# USB_Hub.net
KiCad netlist of a schematic drawn in Altium Designer
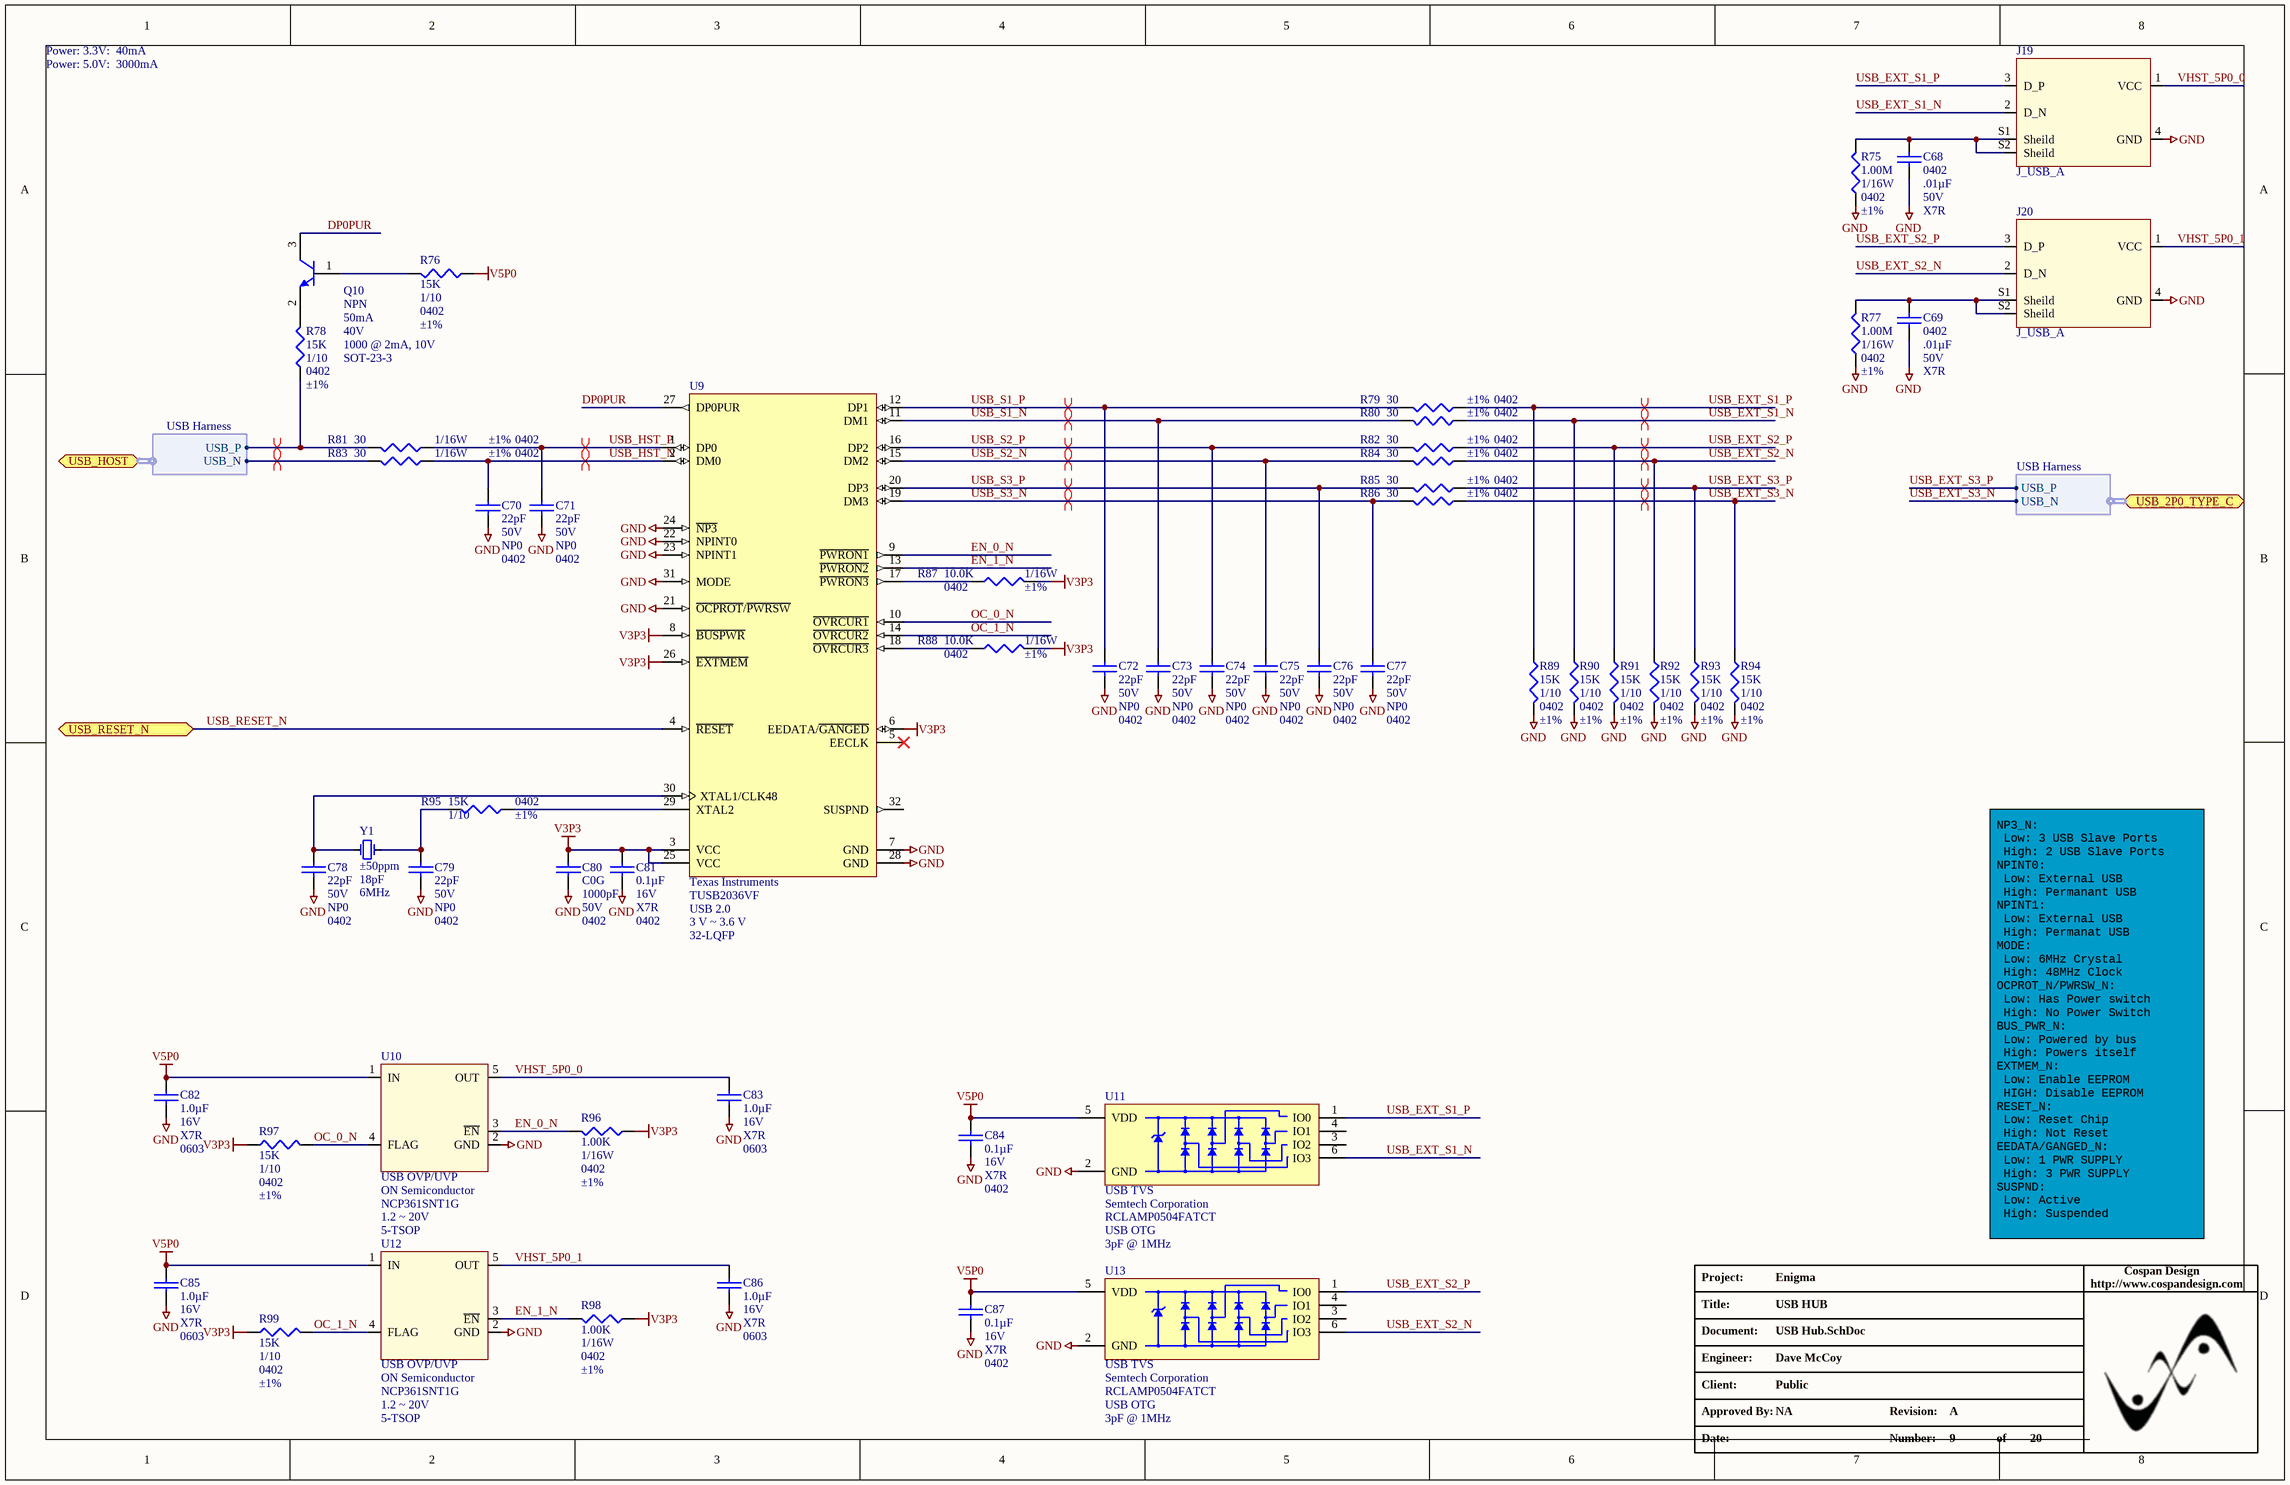
[diagram p0: USB Hub.SchDoc]

(export (version "E")
  (design (tool "Eeschema 10.0.6"))
  (components
    (comp (ref "C68")
      (value "10000pF")
      (footprint "C_0402")
      (description "CAP CERAMIC .01UF 50V X7R 0402")
      (fields
        (field (name "MANUFACTURER") "Murata Electronics North America")
        (field (name "MANUFACTURER PART NUMBER") "GRM155R71H103KA88D")
        (field (name "PACKAGE / CASE") "0402")
        (field (name "CAPACITANCE") ".01µF")
        (field (name "VOLTAGE - RATED") "50V")
        (field (name "TEMPERATURE COEFFICIENT") "X7R")
      )
      (libsource (lib "Main Library") (part "C_0402_10000PF_50V"))
    )
    (comp (ref "C69")
      (value "10000pF")
      (footprint "C_0402")
      (description "CAP CERAMIC .01UF 50V X7R 0402")
      (fields
        (field (name "MANUFACTURER") "Murata Electronics North America")
        (field (name "MANUFACTURER PART NUMBER") "GRM155R71H103KA88D")
        (field (name "PACKAGE / CASE") "0402")
        (field (name "CAPACITANCE") ".01µF")
        (field (name "VOLTAGE - RATED") "50V")
        (field (name "TEMPERATURE COEFFICIENT") "X7R")
      )
      (libsource (lib "Main Library") (part "C_0402_10000PF_50V"))
    )
    (comp (ref "C70")
      (value "22pF")
      (footprint "C_ERA-0402")
      (description "CAP CER 22PF 50V NP0 0402")
      (fields
        (field (name "MANUFACTURER") "Murata Electronics North America")
        (field (name "MANUFACTURER PART NUMBER") "GRM1555C1H220FA01D")
        (field (name "CAPACITANCE") "22pF")
        (field (name "VOLTAGE - RATED") "50V")
        (field (name "TEMPERATURE COEFFICIENT") "NP0")
        (field (name "PACKAGE / CASE") "0402")
      )
      (libsource (lib "Main LibraryX") (part "C_0402_22PF_50V"))
    )
    (comp (ref "C71")
      (value "22pF")
      (footprint "C_ERA-0402")
      (description "CAP CER 22PF 50V NP0 0402")
      (fields
        (field (name "MANUFACTURER") "Murata Electronics North America")
        (field (name "MANUFACTURER PART NUMBER") "GRM1555C1H220FA01D")
        (field (name "CAPACITANCE") "22pF")
        (field (name "VOLTAGE - RATED") "50V")
        (field (name "TEMPERATURE COEFFICIENT") "NP0")
        (field (name "PACKAGE / CASE") "0402")
      )
      (libsource (lib "Main LibraryX") (part "C_0402_22PF_50V"))
    )
    (comp (ref "C72")
      (value "22pF")
      (footprint "C_ERA-0402")
      (description "CAP CER 22PF 50V NP0 0402")
      (fields
        (field (name "MANUFACTURER") "Murata Electronics North America")
        (field (name "MANUFACTURER PART NUMBER") "GRM1555C1H220FA01D")
        (field (name "CAPACITANCE") "22pF")
        (field (name "VOLTAGE - RATED") "50V")
        (field (name "TEMPERATURE COEFFICIENT") "NP0")
        (field (name "PACKAGE / CASE") "0402")
      )
      (libsource (lib "Main LibraryX") (part "C_0402_22PF_50V"))
    )
    (comp (ref "C73")
      (value "22pF")
      (footprint "C_ERA-0402")
      (description "CAP CER 22PF 50V NP0 0402")
      (fields
        (field (name "MANUFACTURER") "Murata Electronics North America")
        (field (name "MANUFACTURER PART NUMBER") "GRM1555C1H220FA01D")
        (field (name "CAPACITANCE") "22pF")
        (field (name "VOLTAGE - RATED") "50V")
        (field (name "TEMPERATURE COEFFICIENT") "NP0")
        (field (name "PACKAGE / CASE") "0402")
      )
      (libsource (lib "Main LibraryX") (part "C_0402_22PF_50V"))
    )
    (comp (ref "C74")
      (value "22pF")
      (footprint "C_ERA-0402")
      (description "CAP CER 22PF 50V NP0 0402")
      (fields
        (field (name "MANUFACTURER") "Murata Electronics North America")
        (field (name "MANUFACTURER PART NUMBER") "GRM1555C1H220FA01D")
        (field (name "CAPACITANCE") "22pF")
        (field (name "VOLTAGE - RATED") "50V")
        (field (name "TEMPERATURE COEFFICIENT") "NP0")
        (field (name "PACKAGE / CASE") "0402")
      )
      (libsource (lib "Main LibraryX") (part "C_0402_22PF_50V"))
    )
    (comp (ref "C75")
      (value "22pF")
      (footprint "C_ERA-0402")
      (description "CAP CER 22PF 50V NP0 0402")
      (fields
        (field (name "MANUFACTURER") "Murata Electronics North America")
        (field (name "MANUFACTURER PART NUMBER") "GRM1555C1H220FA01D")
        (field (name "CAPACITANCE") "22pF")
        (field (name "VOLTAGE - RATED") "50V")
        (field (name "TEMPERATURE COEFFICIENT") "NP0")
        (field (name "PACKAGE / CASE") "0402")
      )
      (libsource (lib "Main LibraryX") (part "C_0402_22PF_50V"))
    )
    (comp (ref "C76")
      (value "22pF")
      (footprint "C_ERA-0402")
      (description "CAP CER 22PF 50V NP0 0402")
      (fields
        (field (name "MANUFACTURER") "Murata Electronics North America")
        (field (name "MANUFACTURER PART NUMBER") "GRM1555C1H220FA01D")
        (field (name "CAPACITANCE") "22pF")
        (field (name "VOLTAGE - RATED") "50V")
        (field (name "TEMPERATURE COEFFICIENT") "NP0")
        (field (name "PACKAGE / CASE") "0402")
      )
      (libsource (lib "Main LibraryX") (part "C_0402_22PF_50V"))
    )
    (comp (ref "C77")
      (value "22pF")
      (footprint "C_ERA-0402")
      (description "CAP CER 22PF 50V NP0 0402")
      (fields
        (field (name "MANUFACTURER") "Murata Electronics North America")
        (field (name "MANUFACTURER PART NUMBER") "GRM1555C1H220FA01D")
        (field (name "CAPACITANCE") "22pF")
        (field (name "VOLTAGE - RATED") "50V")
        (field (name "TEMPERATURE COEFFICIENT") "NP0")
        (field (name "PACKAGE / CASE") "0402")
      )
      (libsource (lib "Main LibraryX") (part "C_0402_22PF_50V"))
    )
    (comp (ref "C78")
      (value "22pF")
      (footprint "C_ERA-0402")
      (description "CAP CER 22PF 50V NP0 0402")
      (fields
        (field (name "MANUFACTURER") "Murata Electronics North America")
        (field (name "MANUFACTURER PART NUMBER") "GRM1555C1H220FA01D")
        (field (name "CAPACITANCE") "22pF")
        (field (name "VOLTAGE - RATED") "50V")
        (field (name "TEMPERATURE COEFFICIENT") "NP0")
        (field (name "PACKAGE / CASE") "0402")
      )
      (libsource (lib "Main LibraryX") (part "C_0402_22PF_50V"))
    )
    (comp (ref "C79")
      (value "22pF")
      (footprint "C_ERA-0402")
      (description "CAP CER 22PF 50V NP0 0402")
      (fields
        (field (name "MANUFACTURER") "Murata Electronics North America")
        (field (name "MANUFACTURER PART NUMBER") "GRM1555C1H220FA01D")
        (field (name "CAPACITANCE") "22pF")
        (field (name "VOLTAGE - RATED") "50V")
        (field (name "TEMPERATURE COEFFICIENT") "NP0")
        (field (name "PACKAGE / CASE") "0402")
      )
      (libsource (lib "Main LibraryX") (part "C_0402_22PF_50V"))
    )
    (comp (ref "C80")
      (value "1000pF")
      (footprint "C_0402")
      (description "CAP CER 1000PF 50V C0G 0402")
      (fields
        (field (name "MANUFACTURER") "Murata Electronics North America")
        (field (name "MANUFACTURER PART NUMBER") "GRM1555C1H102JA01D")
        (field (name "TEMPERATURE COEFFICIENT") "C0G")
        (field (name "CAPACITANCE") "1000pF")
        (field (name "VOLTAGE - RATED") "50V")
        (field (name "PACKAGE / CASE") "0402")
      )
      (libsource (lib "Main Library") (part "C_0402_1000PF_50V"))
    )
    (comp (ref "C81")
      (value "0.1uF")
      (footprint "C_0402")
      (description "CAP CER .10UF 16V X7R 0402")
      (fields
        (field (name "MANUFACTURER") "Murata Electronics North America")
        (field (name "MANUFACTURER PART NUMBER") "GRM155R71C104KA88J")
        (field (name "CAPACITANCE") "0.1µF")
        (field (name "VOLTAGE - RATED") "16V")
        (field (name "TEMPERATURE COEFFICIENT") "X7R")
        (field (name "PACKAGE / CASE") "0402")
      )
      (libsource (lib "Main LibraryX") (part "C_0402_0.1UF_16V"))
    )
    (comp (ref "C82")
      (value "1.0uF")
      (footprint "C_ERA-0603")
      (description "CAP CER 1UF 16V 10% X7R 0603")
      (fields
        (field (name "MANUFACTURER") "Yageo")
        (field (name "MANUFACTURER PART NUMBER") "CC0603KRX7R7BB105")
        (field (name "CAPACITANCE") "1.0µF")
        (field (name "VOLTAGE - RATED") "16V")
        (field (name "TEMPERATURE COEFFICIENT") "X7R")
        (field (name "PACKAGE / CASE") "0603")
      )
      (libsource (lib "Main LibraryX") (part "C_0603_1.0uF_16V"))
    )
    (comp (ref "C83")
      (value "1.0uF")
      (footprint "C_ERA-0603")
      (description "CAP CER 1UF 16V 10% X7R 0603")
      (fields
        (field (name "MANUFACTURER") "Yageo")
        (field (name "MANUFACTURER PART NUMBER") "CC0603KRX7R7BB105")
        (field (name "CAPACITANCE") "1.0µF")
        (field (name "VOLTAGE - RATED") "16V")
        (field (name "TEMPERATURE COEFFICIENT") "X7R")
        (field (name "PACKAGE / CASE") "0603")
      )
      (libsource (lib "Main LibraryX") (part "C_0603_1.0uF_16V"))
    )
    (comp (ref "C84")
      (value "0.1uF")
      (footprint "C_0402")
      (description "CAP CER .10UF 16V X7R 0402")
      (fields
        (field (name "MANUFACTURER") "Murata Electronics North America")
        (field (name "MANUFACTURER PART NUMBER") "GRM155R71C104KA88J")
        (field (name "CAPACITANCE") "0.1µF")
        (field (name "VOLTAGE - RATED") "16V")
        (field (name "TEMPERATURE COEFFICIENT") "X7R")
        (field (name "PACKAGE / CASE") "0402")
      )
      (libsource (lib "Main LibraryX") (part "C_0402_0.1UF_16V"))
    )
    (comp (ref "C85")
      (value "1.0uF")
      (footprint "C_ERA-0603")
      (description "CAP CER 1UF 16V 10% X7R 0603")
      (fields
        (field (name "MANUFACTURER") "Yageo")
        (field (name "MANUFACTURER PART NUMBER") "CC0603KRX7R7BB105")
        (field (name "CAPACITANCE") "1.0µF")
        (field (name "VOLTAGE - RATED") "16V")
        (field (name "TEMPERATURE COEFFICIENT") "X7R")
        (field (name "PACKAGE / CASE") "0603")
      )
      (libsource (lib "Main LibraryX") (part "C_0603_1.0uF_16V"))
    )
    (comp (ref "C86")
      (value "1.0uF")
      (footprint "C_ERA-0603")
      (description "CAP CER 1UF 16V 10% X7R 0603")
      (fields
        (field (name "MANUFACTURER") "Yageo")
        (field (name "MANUFACTURER PART NUMBER") "CC0603KRX7R7BB105")
        (field (name "CAPACITANCE") "1.0µF")
        (field (name "VOLTAGE - RATED") "16V")
        (field (name "TEMPERATURE COEFFICIENT") "X7R")
        (field (name "PACKAGE / CASE") "0603")
      )
      (libsource (lib "Main LibraryX") (part "C_0603_1.0uF_16V"))
    )
    (comp (ref "C87")
      (value "0.1uF")
      (footprint "C_0402")
      (description "CAP CER .10UF 16V X7R 0402")
      (fields
        (field (name "MANUFACTURER") "Murata Electronics North America")
        (field (name "MANUFACTURER PART NUMBER") "GRM155R71C104KA88J")
        (field (name "CAPACITANCE") "0.1µF")
        (field (name "VOLTAGE - RATED") "16V")
        (field (name "TEMPERATURE COEFFICIENT") "X7R")
        (field (name "PACKAGE / CASE") "0402")
      )
      (libsource (lib "Main LibraryX") (part "C_0402_0.1UF_16V"))
    )
    (comp (ref "J19")
      (value "J_USB_A")
      (footprint "USB_A")
      (description "CONN PLUG USB A 4POS SMD R/A")
      (fields
        (field (name "MANUFACTURER") "Molex Inc")
        (field (name "MANUFACTURER PART NUMBER") "0480372200")
      )
      (libsource (lib "Main Library") (part "J_USB_A"))
    )
    (comp (ref "J20")
      (value "J_USB_A")
      (footprint "USB_A")
      (description "CONN PLUG USB A 4POS SMD R/A")
      (fields
        (field (name "MANUFACTURER") "Molex Inc")
        (field (name "MANUFACTURER PART NUMBER") "0480372200")
      )
      (libsource (lib "Main Library") (part "J_USB_A"))
    )
    (comp (ref "Q10")
      (value "NPN")
      (footprint "SOT-23A")
      (description "TRANS NPN 40V 50MA MINI3")
      (fields
        (field (name "MANUFACTURER") "Panasonic Electronic Components - Semiconductor Products")
        (field (name "MANUFACTURER PART NUMBER") "DSC2A01T0L")
        (field (name "TRANSISTOR TYPE") "NPN")
        (field (name "CURRENT - COLLECTOR (IC) (MAX)") "50mA")
        (field (name "VOLTAGE - COLLECTOR EMITTER BREAKDOWN (MAX)") "40V")
        (field (name "DC CURRENT GAIN (HFE) (MIN) @ IC, VCE") "1000 @ 2mA, 10V")
        (field (name "PACKAGE / CASE") "SOT-23-3")
      )
      (libsource (lib "Main Library") (part "Q_NPN_40MA_HFE_1000"))
    )
    (comp (ref "R75")
      (value "1.0M Ohms")
      (footprint "R_0402")
      (description "RES 1.00M OHM 1/16W 1% 0402 SMD")
      (fields
        (field (name "MANUFACTURER") "Yageo")
        (field (name "MANUFACTURER PART NUMBER") "RC0402FR-071ML")
        (field (name "RESISTANCE IN OHMS") "1.00M")
        (field (name "POWER (WATTS)") "1/16W")
        (field (name "CASE") "0402")
        (field (name "TOLERANCE") "±1%")
      )
      (libsource (lib "Main LibraryX") (part "R_0402_1.0M"))
    )
    (comp (ref "R76")
      (value "R_0402_15.0K")
      (footprint "R_0402")
      (description "RES 15.0K OHM 1/10W 1% 0402 SMD")
      (fields
        (field (name "MANUFACTURER") "Panasonic - ECG")
        (field (name "MANUFACTURER PART NUMBER") "ERJ-2RKF1502X")
        (field (name "RESISTANCE IN OHMS") "15K")
        (field (name "POWER (WATTS)") "1/10")
        (field (name "CASE") "0402")
        (field (name "TOLERANCE") "±1%")
      )
      (libsource (lib "Main Library") (part "R_0402_15.0K"))
    )
    (comp (ref "R77")
      (value "1.0M Ohms")
      (footprint "R_0402")
      (description "RES 1.00M OHM 1/16W 1% 0402 SMD")
      (fields
        (field (name "MANUFACTURER") "Yageo")
        (field (name "MANUFACTURER PART NUMBER") "RC0402FR-071ML")
        (field (name "RESISTANCE IN OHMS") "1.00M")
        (field (name "POWER (WATTS)") "1/16W")
        (field (name "CASE") "0402")
        (field (name "TOLERANCE") "±1%")
      )
      (libsource (lib "Main LibraryX") (part "R_0402_1.0M"))
    )
    (comp (ref "R78")
      (value "R_0402_15.0K")
      (footprint "R_0402")
      (description "RES 15.0K OHM 1/10W 1% 0402 SMD")
      (fields
        (field (name "MANUFACTURER") "Panasonic - ECG")
        (field (name "MANUFACTURER PART NUMBER") "ERJ-2RKF1502X")
        (field (name "RESISTANCE IN OHMS") "15K")
        (field (name "POWER (WATTS)") "1/10")
        (field (name "CASE") "0402")
        (field (name "TOLERANCE") "±1%")
      )
      (libsource (lib "Main Library") (part "R_0402_15.0K"))
    )
    (comp (ref "R79")
      (value "R_0402_30")
      (footprint "R_0402")
      (description "RES SMD 30 OHM 1% 1/10W 0402")
      (fields
        (field (name "MANUFACTURER") "Panasonic Electronic Components")
        (field (name "MANUFACTURER PART NUMBER") "ERJ-2RKF30R0X")
        (field (name "RESISTANCE IN OHMS") "30")
        (field (name "CASE") "0402")
        (field (name "TOLERANCE") "±1%")
      )
      (libsource (lib "Cospan Design") (part "R_0402_30"))
    )
    (comp (ref "R80")
      (value "R_0402_30")
      (footprint "R_0402")
      (description "RES SMD 30 OHM 1% 1/10W 0402")
      (fields
        (field (name "MANUFACTURER") "Panasonic Electronic Components")
        (field (name "MANUFACTURER PART NUMBER") "ERJ-2RKF30R0X")
        (field (name "RESISTANCE IN OHMS") "30")
        (field (name "CASE") "0402")
        (field (name "TOLERANCE") "±1%")
      )
      (libsource (lib "Cospan Design") (part "R_0402_30"))
    )
    (comp (ref "R81")
      (value "R_0402_30")
      (footprint "R_0402")
      (description "RES SMD 30 OHM 1% 1/10W 0402")
      (fields
        (field (name "MANUFACTURER") "Panasonic Electronic Components")
        (field (name "MANUFACTURER PART NUMBER") "ERJ-2RKF30R0X")
        (field (name "RESISTANCE IN OHMS") "30")
        (field (name "POWER (WATTS)") "1/16W")
        (field (name "CASE") "0402")
        (field (name "TOLERANCE") "±1%")
      )
      (libsource (lib "Cospan Design") (part "R_0402_30"))
    )
    (comp (ref "R82")
      (value "R_0402_30")
      (footprint "R_0402")
      (description "RES SMD 30 OHM 1% 1/10W 0402")
      (fields
        (field (name "MANUFACTURER") "Panasonic Electronic Components")
        (field (name "MANUFACTURER PART NUMBER") "ERJ-2RKF30R0X")
        (field (name "RESISTANCE IN OHMS") "30")
        (field (name "CASE") "0402")
        (field (name "TOLERANCE") "±1%")
      )
      (libsource (lib "Cospan Design") (part "R_0402_30"))
    )
    (comp (ref "R83")
      (value "R_0402_30")
      (footprint "R_0402")
      (description "RES SMD 30 OHM 1% 1/10W 0402")
      (fields
        (field (name "MANUFACTURER") "Panasonic Electronic Components")
        (field (name "MANUFACTURER PART NUMBER") "ERJ-2RKF30R0X")
        (field (name "RESISTANCE IN OHMS") "30")
        (field (name "POWER (WATTS)") "1/16W")
        (field (name "CASE") "0402")
        (field (name "TOLERANCE") "±1%")
      )
      (libsource (lib "Cospan Design") (part "R_0402_30"))
    )
    (comp (ref "R84")
      (value "R_0402_30")
      (footprint "R_0402")
      (description "RES SMD 30 OHM 1% 1/10W 0402")
      (fields
        (field (name "MANUFACTURER") "Panasonic Electronic Components")
        (field (name "MANUFACTURER PART NUMBER") "ERJ-2RKF30R0X")
        (field (name "RESISTANCE IN OHMS") "30")
        (field (name "CASE") "0402")
        (field (name "TOLERANCE") "±1%")
      )
      (libsource (lib "Cospan Design") (part "R_0402_30"))
    )
    (comp (ref "R85")
      (value "R_0402_30")
      (footprint "R_0402")
      (description "RES SMD 30 OHM 1% 1/10W 0402")
      (fields
        (field (name "MANUFACTURER") "Panasonic Electronic Components")
        (field (name "MANUFACTURER PART NUMBER") "ERJ-2RKF30R0X")
        (field (name "RESISTANCE IN OHMS") "30")
        (field (name "CASE") "0402")
        (field (name "TOLERANCE") "±1%")
      )
      (libsource (lib "Cospan Design") (part "R_0402_30"))
    )
    (comp (ref "R86")
      (value "R_0402_30")
      (footprint "R_0402")
      (description "RES SMD 30 OHM 1% 1/10W 0402")
      (fields
        (field (name "MANUFACTURER") "Panasonic Electronic Components")
        (field (name "MANUFACTURER PART NUMBER") "ERJ-2RKF30R0X")
        (field (name "RESISTANCE IN OHMS") "30")
        (field (name "CASE") "0402")
        (field (name "TOLERANCE") "±1%")
      )
      (libsource (lib "Cospan Design") (part "R_0402_30"))
    )
    (comp (ref "R87")
      (value "R_0402_10.0K")
      (footprint "R_0402")
      (description "RES 10.0K OHM 1/16W 1% 0402 SMD")
      (fields
        (field (name "MANUFACTURER") "Stackpole Electronics Inc")
        (field (name "MANUFACTURER PART NUMBER") "RMCF0402FT10K0")
        (field (name "RESISTANCE IN OHMS") "10.0K")
        (field (name "POWER (WATTS)") "1/16W")
        (field (name "CASE") "0402")
        (field (name "TOLERANCE") "±1%")
      )
      (libsource (lib "Cospan Design") (part "R_0402_10.0K"))
    )
    (comp (ref "R88")
      (value "R_0402_10.0K")
      (footprint "R_0402")
      (description "RES 10.0K OHM 1/16W 1% 0402 SMD")
      (fields
        (field (name "MANUFACTURER") "Stackpole Electronics Inc")
        (field (name "MANUFACTURER PART NUMBER") "RMCF0402FT10K0")
        (field (name "RESISTANCE IN OHMS") "10.0K")
        (field (name "POWER (WATTS)") "1/16W")
        (field (name "CASE") "0402")
        (field (name "TOLERANCE") "±1%")
      )
      (libsource (lib "Cospan Design") (part "R_0402_10.0K"))
    )
    (comp (ref "R89")
      (value "R_0402_15.0K")
      (footprint "R_0402")
      (description "RES 15.0K OHM 1/10W 1% 0402 SMD")
      (fields
        (field (name "MANUFACTURER") "Panasonic - ECG")
        (field (name "MANUFACTURER PART NUMBER") "ERJ-2RKF1502X")
        (field (name "RESISTANCE IN OHMS") "15K")
        (field (name "POWER (WATTS)") "1/10")
        (field (name "CASE") "0402")
        (field (name "TOLERANCE") "±1%")
      )
      (libsource (lib "Main Library") (part "R_0402_15.0K"))
    )
    (comp (ref "R90")
      (value "R_0402_15.0K")
      (footprint "R_0402")
      (description "RES 15.0K OHM 1/10W 1% 0402 SMD")
      (fields
        (field (name "MANUFACTURER") "Panasonic - ECG")
        (field (name "MANUFACTURER PART NUMBER") "ERJ-2RKF1502X")
        (field (name "RESISTANCE IN OHMS") "15K")
        (field (name "POWER (WATTS)") "1/10")
        (field (name "CASE") "0402")
        (field (name "TOLERANCE") "±1%")
      )
      (libsource (lib "Main Library") (part "R_0402_15.0K"))
    )
    (comp (ref "R91")
      (value "R_0402_15.0K")
      (footprint "R_0402")
      (description "RES 15.0K OHM 1/10W 1% 0402 SMD")
      (fields
        (field (name "MANUFACTURER") "Panasonic - ECG")
        (field (name "MANUFACTURER PART NUMBER") "ERJ-2RKF1502X")
        (field (name "RESISTANCE IN OHMS") "15K")
        (field (name "POWER (WATTS)") "1/10")
        (field (name "CASE") "0402")
        (field (name "TOLERANCE") "±1%")
      )
      (libsource (lib "Main Library") (part "R_0402_15.0K"))
    )
    (comp (ref "R92")
      (value "R_0402_15.0K")
      (footprint "R_0402")
      (description "RES 15.0K OHM 1/10W 1% 0402 SMD")
      (fields
        (field (name "MANUFACTURER") "Panasonic - ECG")
        (field (name "MANUFACTURER PART NUMBER") "ERJ-2RKF1502X")
        (field (name "RESISTANCE IN OHMS") "15K")
        (field (name "POWER (WATTS)") "1/10")
        (field (name "CASE") "0402")
        (field (name "TOLERANCE") "±1%")
      )
      (libsource (lib "Main Library") (part "R_0402_15.0K"))
    )
    (comp (ref "R93")
      (value "R_0402_15.0K")
      (footprint "R_0402")
      (description "RES 15.0K OHM 1/10W 1% 0402 SMD")
      (fields
        (field (name "MANUFACTURER") "Panasonic - ECG")
        (field (name "MANUFACTURER PART NUMBER") "ERJ-2RKF1502X")
        (field (name "RESISTANCE IN OHMS") "15K")
        (field (name "POWER (WATTS)") "1/10")
        (field (name "CASE") "0402")
        (field (name "TOLERANCE") "±1%")
      )
      (libsource (lib "Main Library") (part "R_0402_15.0K"))
    )
    (comp (ref "R94")
      (value "R_0402_15.0K")
      (footprint "R_0402")
      (description "RES 15.0K OHM 1/10W 1% 0402 SMD")
      (fields
        (field (name "MANUFACTURER") "Panasonic - ECG")
        (field (name "MANUFACTURER PART NUMBER") "ERJ-2RKF1502X")
        (field (name "RESISTANCE IN OHMS") "15K")
        (field (name "POWER (WATTS)") "1/10")
        (field (name "CASE") "0402")
        (field (name "TOLERANCE") "±1%")
      )
      (libsource (lib "Main Library") (part "R_0402_15.0K"))
    )
    (comp (ref "R95")
      (value "R_0402_15.0K")
      (footprint "R_0402")
      (description "RES 15.0K OHM 1/10W 1% 0402 SMD")
      (fields
        (field (name "MANUFACTURER") "Panasonic - ECG")
        (field (name "MANUFACTURER PART NUMBER") "ERJ-2RKF1502X")
        (field (name "RESISTANCE IN OHMS") "15K")
        (field (name "POWER (WATTS)") "1/10")
        (field (name "CASE") "0402")
        (field (name "TOLERANCE") "±1%")
      )
      (libsource (lib "Main Library") (part "R_0402_15.0K"))
    )
    (comp (ref "R96")
      (value "1.0k Ohms")
      (footprint "R_0402")
      (description "RES 1.00K OHM 1/16W 1% 0402 SMD")
      (fields
        (field (name "MANUFACTURER") "Yageo")
        (field (name "MANUFACTURER PART NUMBER") "RC0402FR-071KL")
        (field (name "RESISTANCE IN OHMS") "1.00K")
        (field (name "POWER (WATTS)") "1/16W")
        (field (name "CASE") "0402")
        (field (name "TOLERANCE") "±1%")
      )
      (libsource (lib "Main Library") (part "R_0402_1.0K"))
    )
    (comp (ref "R97")
      (value "R_0402_15.0K")
      (footprint "R_0402")
      (description "RES 15.0K OHM 1/10W 1% 0402 SMD")
      (fields
        (field (name "MANUFACTURER") "Panasonic - ECG")
        (field (name "MANUFACTURER PART NUMBER") "ERJ-2RKF1502X")
        (field (name "RESISTANCE IN OHMS") "15K")
        (field (name "POWER (WATTS)") "1/10")
        (field (name "CASE") "0402")
        (field (name "TOLERANCE") "±1%")
      )
      (libsource (lib "Main Library") (part "R_0402_15.0K"))
    )
    (comp (ref "R98")
      (value "1.0k Ohms")
      (footprint "R_0402")
      (description "RES 1.00K OHM 1/16W 1% 0402 SMD")
      (fields
        (field (name "MANUFACTURER") "Yageo")
        (field (name "MANUFACTURER PART NUMBER") "RC0402FR-071KL")
        (field (name "RESISTANCE IN OHMS") "1.00K")
        (field (name "POWER (WATTS)") "1/16W")
        (field (name "CASE") "0402")
        (field (name "TOLERANCE") "±1%")
      )
      (libsource (lib "Main Library") (part "R_0402_1.0K"))
    )
    (comp (ref "R99")
      (value "R_0402_15.0K")
      (footprint "R_0402")
      (description "RES 15.0K OHM 1/10W 1% 0402 SMD")
      (fields
        (field (name "MANUFACTURER") "Panasonic - ECG")
        (field (name "MANUFACTURER PART NUMBER") "ERJ-2RKF1502X")
        (field (name "RESISTANCE IN OHMS") "15K")
        (field (name "POWER (WATTS)") "1/10")
        (field (name "CASE") "0402")
        (field (name "TOLERANCE") "±1%")
      )
      (libsource (lib "Main Library") (part "R_0402_15.0K"))
    )
    (comp (ref "U9")
      (value "U_TI-TUSB2036-LQFP_VF-32")
      (footprint "VF32_L")
      (description "IC HUB CONTROLLER USB 2.0 32LQFP")
      (fields
        (field (name "MANUFACTURER") "Texas Instruments")
        (field (name "MANUFACTURER PART NUMBER") "TUSB2036VF")
        (field (name "STANDARDS") "USB 2.0")
        (field (name "VOLTAGE - SUPPLY") "3 V ~ 3.6 V")
        (field (name "PACKAGE / CASE") "32-LQFP")
      )
      (libsource (lib "Cospan Design") (part "U_TI-TUSB2036-LQFP_VF-32"))
    )
    (comp (ref "U10")
      (value "USB OVP/UVP")
      (footprint "SOT95P280X90-5N")
      (description "IC USB POS OVP/OCP 5TSOP")
      (fields
        (field (name "MANUFACTURER") "ON Semiconductor")
        (field (name "MANUFACTURER PART NUMBER") "NCP361SNT1G")
        (field (name "VOLTAGE - WORKING") "1.2 ~ 20V")
        (field (name "SUPPLIER DEVICE PACKAGE") "5-TSOP")
      )
      (libsource (lib "Main Library") (part "U_NCP361SNT1G"))
    )
    (comp (ref "U11")
      (value "USB TVS")
      (footprint "SC70-LT6_N")
      (description "TVS DIODE 5VWM 25VC SC70-6")
      (fields
        (field (name "MANUFACTURER") "Semtech Corporation")
        (field (name "MANUFACTURER PART NUMBER") "RCLAMP0504FATCT")
        (field (name "APPLICATIONS") "USB OTG")
        (field (name "CAPACITANCE @ FREQUENCY") "3pF @ 1MHz")
      )
      (libsource (lib "Main Library") (part "U_USB_TVS_SCV70"))
    )
    (comp (ref "U12")
      (value "USB OVP/UVP")
      (footprint "SOT95P280X90-5N")
      (description "IC USB POS OVP/OCP 5TSOP")
      (fields
        (field (name "MANUFACTURER") "ON Semiconductor")
        (field (name "MANUFACTURER PART NUMBER") "NCP361SNT1G")
        (field (name "VOLTAGE - WORKING") "1.2 ~ 20V")
        (field (name "SUPPLIER DEVICE PACKAGE") "5-TSOP")
      )
      (libsource (lib "Main Library") (part "U_NCP361SNT1G"))
    )
    (comp (ref "U13")
      (value "USB TVS")
      (footprint "SC70-LT6_N")
      (description "TVS DIODE 5VWM 25VC SC70-6")
      (fields
        (field (name "MANUFACTURER") "Semtech Corporation")
        (field (name "MANUFACTURER PART NUMBER") "RCLAMP0504FATCT")
        (field (name "APPLICATIONS") "USB OTG")
        (field (name "CAPACITANCE @ FREQUENCY") "3pF @ 1MHz")
      )
      (libsource (lib "Main Library") (part "U_USB_TVS_SCV70"))
    )
    (comp (ref "Y1")
      (value "6.00MHz Crystal")
      (footprint "HC49")
      (description "CRYSTAL 6.0000MHZ 18PF SMD")
      (fields
        (field (name "MANUFACTURER") "Abracon LLC")
        (field (name "MANUFACTURER PART NUMBER") "ABLS-6.000MHZ-D-T")
        (field (name "FREQUENCY STABILITY") "±50ppm")
        (field (name "LOAD CAPACITANCE") "18pF")
        (field (name "FREQUENCY") "6MHz")
      )
      (libsource (lib "Main Library") (part "Y_SMD_6.00MHZ_18PF"))
    )
  )
  (nets
    (net (code "3") (name "/DP0PUR") (class "Default")
      (node (ref "Q10") (pin "3") (pinfunction "C_3") (pintype "passive"))
      (node (ref "U9") (pin "27") (pinfunction "DP0PUR_27") (pintype "output"))
    )
    (net (code "4") (name "/EN_0_N") (class "Default")
      (node (ref "R96") (pin "1") (pinfunction "1_1") (pintype "passive"))
      (node (ref "U10") (pin "3") (pinfunction "~{EN}_3") (pintype "passive"))
      (node (ref "U9") (pin "9") (pinfunction "~{PWRON1}_9") (pintype "output"))
    )
    (net (code "5") (name "/EN_1_N") (class "Default")
      (node (ref "R98") (pin "1") (pinfunction "1_1") (pintype "passive"))
      (node (ref "U12") (pin "3") (pinfunction "~{EN}_3") (pintype "passive"))
      (node (ref "U9") (pin "13") (pinfunction "~{PWRON2}_13") (pintype "output"))
    )
    (net (code "6") (name "/OC_0_N") (class "Default")
      (node (ref "R97") (pin "1") (pinfunction "1_1") (pintype "passive"))
      (node (ref "U10") (pin "4") (pinfunction "FLAG_4") (pintype "passive"))
      (node (ref "U9") (pin "10") (pinfunction "~{OVRCUR1}_10") (pintype "input"))
    )
    (net (code "7") (name "/OC_1_N") (class "Default")
      (node (ref "R99") (pin "1") (pinfunction "1_1") (pintype "passive"))
      (node (ref "U12") (pin "4") (pinfunction "FLAG_4") (pintype "passive"))
      (node (ref "U9") (pin "14") (pinfunction "~{OVRCUR2}_14") (pintype "input"))
    )
    (net (code "8") (name "/USB_EXT_S1_N") (class "Default")
      (node (ref "J19") (pin "2") (pinfunction "D_N_2") (pintype "passive"))
      (node (ref "R80") (pin "2") (pinfunction "2_2") (pintype "passive"))
      (node (ref "R90") (pin "2") (pinfunction "2_2") (pintype "passive"))
      (node (ref "U11") (pin "6") (pinfunction "IO3_6") (pintype "passive"))
    )
    (net (code "9") (name "/USB_EXT_S1_P") (class "Default")
      (node (ref "J19") (pin "3") (pinfunction "D_P_3") (pintype "passive"))
      (node (ref "R79") (pin "2") (pinfunction "2_2") (pintype "passive"))
      (node (ref "R89") (pin "2") (pinfunction "2_2") (pintype "passive"))
      (node (ref "U11") (pin "1") (pinfunction "IO0_1") (pintype "passive"))
    )
    (net (code "10") (name "/USB_EXT_S2_N") (class "Default")
      (node (ref "J20") (pin "2") (pinfunction "D_N_2") (pintype "passive"))
      (node (ref "R84") (pin "2") (pinfunction "2_2") (pintype "passive"))
      (node (ref "R92") (pin "2") (pinfunction "2_2") (pintype "passive"))
      (node (ref "U13") (pin "6") (pinfunction "IO3_6") (pintype "passive"))
    )
    (net (code "11") (name "/USB_EXT_S2_P") (class "Default")
      (node (ref "J20") (pin "3") (pinfunction "D_P_3") (pintype "passive"))
      (node (ref "R82") (pin "2") (pinfunction "2_2") (pintype "passive"))
      (node (ref "R91") (pin "2") (pinfunction "2_2") (pintype "passive"))
      (node (ref "U13") (pin "1") (pinfunction "IO0_1") (pintype "passive"))
    )
    (net (code "12") (name "/USB_EXT_S3_N") (class "Default")
      (node (ref "R86") (pin "2") (pinfunction "2_2") (pintype "passive"))
      (node (ref "R94") (pin "2") (pinfunction "2_2") (pintype "passive"))
    )
    (net (code "13") (name "/USB_EXT_S3_P") (class "Default")
      (node (ref "R85") (pin "2") (pinfunction "2_2") (pintype "passive"))
      (node (ref "R93") (pin "2") (pinfunction "2_2") (pintype "passive"))
    )
    (net (code "14") (name "/USB_HST_N") (class "Default")
      (node (ref "C70") (pin "2") (pinfunction "2_2") (pintype "passive"))
      (node (ref "R83") (pin "2") (pinfunction "2_2") (pintype "passive"))
      (node (ref "U9") (pin "2") (pinfunction "DM0_2") (pintype "bidirectional"))
    )
    (net (code "15") (name "/USB_HST_P") (class "Default")
      (node (ref "C71") (pin "2") (pinfunction "2_2") (pintype "passive"))
      (node (ref "R81") (pin "2") (pinfunction "2_2") (pintype "passive"))
      (node (ref "U9") (pin "1") (pinfunction "DP0_1") (pintype "bidirectional"))
    )
    (net (code "16") (name "/USB_RESET_N") (class "Default")
      (node (ref "U9") (pin "4") (pinfunction "~{RESET}_4") (pintype "input"))
    )
    (net (code "17") (name "/USB_S1_N") (class "Default")
      (node (ref "C73") (pin "2") (pinfunction "2_2") (pintype "passive"))
      (node (ref "R80") (pin "1") (pinfunction "1_1") (pintype "passive"))
      (node (ref "U9") (pin "11") (pinfunction "DM1_11") (pintype "bidirectional"))
    )
    (net (code "18") (name "/USB_S1_P") (class "Default")
      (node (ref "C72") (pin "2") (pinfunction "2_2") (pintype "passive"))
      (node (ref "R79") (pin "1") (pinfunction "1_1") (pintype "passive"))
      (node (ref "U9") (pin "12") (pinfunction "DP1_12") (pintype "bidirectional"))
    )
    (net (code "19") (name "/USB_S2_N") (class "Default")
      (node (ref "C75") (pin "2") (pinfunction "2_2") (pintype "passive"))
      (node (ref "R84") (pin "1") (pinfunction "1_1") (pintype "passive"))
      (node (ref "U9") (pin "15") (pinfunction "DM2_15") (pintype "bidirectional"))
    )
    (net (code "20") (name "/USB_S2_P") (class "Default")
      (node (ref "C74") (pin "2") (pinfunction "2_2") (pintype "passive"))
      (node (ref "R82") (pin "1") (pinfunction "1_1") (pintype "passive"))
      (node (ref "U9") (pin "16") (pinfunction "DP2_16") (pintype "bidirectional"))
    )
    (net (code "21") (name "/USB_S3_N") (class "Default")
      (node (ref "C77") (pin "2") (pinfunction "2_2") (pintype "passive"))
      (node (ref "R86") (pin "1") (pinfunction "1_1") (pintype "passive"))
      (node (ref "U9") (pin "19") (pinfunction "DM3_19") (pintype "bidirectional"))
    )
    (net (code "22") (name "/USB_S3_P") (class "Default")
      (node (ref "C76") (pin "2") (pinfunction "2_2") (pintype "passive"))
      (node (ref "R85") (pin "1") (pinfunction "1_1") (pintype "passive"))
      (node (ref "U9") (pin "20") (pinfunction "DP3_20") (pintype "bidirectional"))
    )
    (net (code "23") (name "/VHST_5P0_0") (class "Default")
      (node (ref "C83") (pin "2") (pinfunction "2_2") (pintype "passive"))
      (node (ref "J19") (pin "1") (pinfunction "VCC_1") (pintype "passive"))
      (node (ref "U10") (pin "5") (pinfunction "OUT_5") (pintype "passive"))
    )
    (net (code "24") (name "/VHST_5P0_1") (class "Default")
      (node (ref "C86") (pin "2") (pinfunction "2_2") (pintype "passive"))
      (node (ref "J20") (pin "1") (pinfunction "VCC_1") (pintype "passive"))
      (node (ref "U12") (pin "5") (pinfunction "OUT_5") (pintype "passive"))
    )
    (net (code "26") (name "GND") (class "Default")
      (node (ref "C68") (pin "1") (pinfunction "1_1") (pintype "passive"))
      (node (ref "C69") (pin "1") (pinfunction "1_1") (pintype "passive"))
      (node (ref "C70") (pin "1") (pinfunction "1_1") (pintype "passive"))
      (node (ref "C71") (pin "1") (pinfunction "1_1") (pintype "passive"))
      (node (ref "C72") (pin "1") (pinfunction "1_1") (pintype "passive"))
      (node (ref "C73") (pin "1") (pinfunction "1_1") (pintype "passive"))
      (node (ref "C74") (pin "1") (pinfunction "1_1") (pintype "passive"))
      (node (ref "C75") (pin "1") (pinfunction "1_1") (pintype "passive"))
      (node (ref "C76") (pin "1") (pinfunction "1_1") (pintype "passive"))
      (node (ref "C77") (pin "1") (pinfunction "1_1") (pintype "passive"))
      (node (ref "C78") (pin "1") (pinfunction "1_1") (pintype "passive"))
      (node (ref "C79") (pin "1") (pinfunction "1_1") (pintype "passive"))
      (node (ref "C80") (pin "1") (pinfunction "1_1") (pintype "passive"))
      (node (ref "C81") (pin "1") (pinfunction "1_1") (pintype "passive"))
      (node (ref "C82") (pin "1") (pinfunction "1_1") (pintype "passive"))
      (node (ref "C83") (pin "1") (pinfunction "1_1") (pintype "passive"))
      (node (ref "C84") (pin "1") (pinfunction "1_1") (pintype "passive"))
      (node (ref "C85") (pin "1") (pinfunction "1_1") (pintype "passive"))
      (node (ref "C86") (pin "1") (pinfunction "1_1") (pintype "passive"))
      (node (ref "C87") (pin "1") (pinfunction "1_1") (pintype "passive"))
      (node (ref "J19") (pin "4") (pinfunction "GND_4") (pintype "passive"))
      (node (ref "J20") (pin "4") (pinfunction "GND_4") (pintype "passive"))
      (node (ref "R75") (pin "2") (pinfunction "2_2") (pintype "passive"))
      (node (ref "R77") (pin "2") (pinfunction "2_2") (pintype "passive"))
      (node (ref "R89") (pin "1") (pinfunction "1_1") (pintype "passive"))
      (node (ref "R90") (pin "1") (pinfunction "1_1") (pintype "passive"))
      (node (ref "R91") (pin "1") (pinfunction "1_1") (pintype "passive"))
      (node (ref "R92") (pin "1") (pinfunction "1_1") (pintype "passive"))
      (node (ref "R93") (pin "1") (pinfunction "1_1") (pintype "passive"))
      (node (ref "R94") (pin "1") (pinfunction "1_1") (pintype "passive"))
      (node (ref "U10") (pin "2") (pinfunction "GND_2") (pintype "passive"))
      (node (ref "U11") (pin "2") (pinfunction "GND_2") (pintype "passive"))
      (node (ref "U12") (pin "2") (pinfunction "GND_2") (pintype "passive"))
      (node (ref "U13") (pin "2") (pinfunction "GND_2") (pintype "passive"))
      (node (ref "U9") (pin "21") (pinfunction "~{OCPROT}/~{PWRSW}_21") (pintype "input"))
      (node (ref "U9") (pin "22") (pinfunction "NPINT0_22") (pintype "input"))
      (node (ref "U9") (pin "23") (pinfunction "NPINT1_23") (pintype "input"))
      (node (ref "U9") (pin "24") (pinfunction "~{NP3}_24") (pintype "input"))
      (node (ref "U9") (pin "28") (pinfunction "GND_28") (pintype "power_in"))
      (node (ref "U9") (pin "31") (pinfunction "MODE_31") (pintype "input"))
      (node (ref "U9") (pin "7") (pinfunction "GND_7") (pintype "power_in"))
    )
    (net (code "27") (name "Net-(C68-Pad2)") (class "Default")
      (node (ref "C68") (pin "2") (pinfunction "2_2") (pintype "passive"))
      (node (ref "J19") (pin "S1") (pinfunction "Sheild_S1") (pintype "passive"))
      (node (ref "J19") (pin "S2") (pinfunction "Sheild_S2") (pintype "passive"))
      (node (ref "R75") (pin "1") (pinfunction "1_1") (pintype "passive"))
    )
    (net (code "28") (name "Net-(C69-Pad2)") (class "Default")
      (node (ref "C69") (pin "2") (pinfunction "2_2") (pintype "passive"))
      (node (ref "J20") (pin "S1") (pinfunction "Sheild_S1") (pintype "passive"))
      (node (ref "J20") (pin "S2") (pinfunction "Sheild_S2") (pintype "passive"))
      (node (ref "R77") (pin "1") (pinfunction "1_1") (pintype "passive"))
    )
    (net (code "29") (name "Net-(C79-Pad2)") (class "Default")
      (node (ref "C79") (pin "2") (pinfunction "2_2") (pintype "passive"))
      (node (ref "R95") (pin "1") (pinfunction "1_1") (pintype "passive"))
      (node (ref "Y1") (pin "1") (pinfunction "1_1") (pintype "passive"))
    )
    (net (code "30") (name "Net-(Q10-B)") (class "Default")
      (node (ref "Q10") (pin "1") (pinfunction "B_1") (pintype "passive"))
      (node (ref "R76") (pin "1") (pinfunction "1_1") (pintype "passive"))
    )
    (net (code "31") (name "Net-(Q10-E)") (class "Default")
      (node (ref "Q10") (pin "2") (pinfunction "E_2") (pintype "passive"))
      (node (ref "R78") (pin "1") (pinfunction "1_1") (pintype "passive"))
    )
    (net (code "32") (name "Net-(R78-Pad2)") (class "Default")
      (node (ref "R78") (pin "2") (pinfunction "2_2") (pintype "passive"))
      (node (ref "R81") (pin "1") (pinfunction "1_1") (pintype "passive"))
    )
    (net (code "33") (name "Net-(U9-XTAL1{slash}CLK48)") (class "Default")
      (node (ref "C78") (pin "2") (pinfunction "2_2") (pintype "passive"))
      (node (ref "U9") (pin "30") (pinfunction "XTAL1/CLK48_30") (pintype "input"))
      (node (ref "Y1") (pin "2") (pinfunction "2_2") (pintype "passive"))
    )
    (net (code "34") (name "Net-(U9-XTAL2)") (class "Default")
      (node (ref "R95") (pin "2") (pinfunction "2_2") (pintype "passive"))
      (node (ref "U9") (pin "29") (pinfunction "XTAL2_29") (pintype "passive"))
    )
    (net (code "35") (name "Net-(U9-~{OVRCUR3})") (class "Default")
      (node (ref "R88") (pin "2") (pinfunction "2_2") (pintype "passive"))
      (node (ref "U9") (pin "18") (pinfunction "~{OVRCUR3}_18") (pintype "input"))
    )
    (net (code "36") (name "Net-(U9-~{PWRON3})") (class "Default")
      (node (ref "R87") (pin "2") (pinfunction "2_2") (pintype "passive"))
      (node (ref "U9") (pin "17") (pinfunction "~{PWRON3}_17") (pintype "output"))
    )
    (net (code "37") (name "V3P3") (class "Default")
      (node (ref "C80") (pin "2") (pinfunction "2_2") (pintype "passive"))
      (node (ref "C81") (pin "2") (pinfunction "2_2") (pintype "passive"))
      (node (ref "R87") (pin "1") (pinfunction "1_1") (pintype "passive"))
      (node (ref "R88") (pin "1") (pinfunction "1_1") (pintype "passive"))
      (node (ref "R96") (pin "2") (pinfunction "2_2") (pintype "passive"))
      (node (ref "R97") (pin "2") (pinfunction "2_2") (pintype "passive"))
      (node (ref "R98") (pin "2") (pinfunction "2_2") (pintype "passive"))
      (node (ref "R99") (pin "2") (pinfunction "2_2") (pintype "passive"))
      (node (ref "U9") (pin "25") (pinfunction "VCC_25") (pintype "power_in"))
      (node (ref "U9") (pin "26") (pinfunction "~{EXTMEM}_26") (pintype "input"))
      (node (ref "U9") (pin "3") (pinfunction "VCC_3") (pintype "power_in"))
      (node (ref "U9") (pin "6") (pinfunction "EEDATA/~{GANGED}_6") (pintype "bidirectional"))
      (node (ref "U9") (pin "8") (pinfunction "~{BUSPWR}_8") (pintype "input"))
    )
    (net (code "38") (name "V5P0") (class "Default")
      (node (ref "C82") (pin "2") (pinfunction "2_2") (pintype "passive"))
      (node (ref "C84") (pin "2") (pinfunction "2_2") (pintype "passive"))
      (node (ref "C85") (pin "2") (pinfunction "2_2") (pintype "passive"))
      (node (ref "C87") (pin "2") (pinfunction "2_2") (pintype "passive"))
      (node (ref "R76") (pin "2") (pinfunction "2_2") (pintype "passive"))
      (node (ref "U10") (pin "1") (pinfunction "IN_1") (pintype "passive"))
      (node (ref "U11") (pin "5") (pinfunction "VDD_5") (pintype "passive"))
      (node (ref "U12") (pin "1") (pinfunction "IN_1") (pintype "passive"))
      (node (ref "U13") (pin "5") (pinfunction "VDD_5") (pintype "passive"))
    )
    (net (code "39") (name "unconnected-(R83-Pad1)") (class "Default")
      (node (ref "R83") (pin "1") (pinfunction "1_1") (pintype "passive"))
    )
    (net (code "40") (name "unconnected-(U9-EECLK-Pad5)") (class "Default")
      (node (ref "U9") (pin "5") (pinfunction "EECLK_5") (pintype "tri_state+no_connect"))
    )
    (net (code "41") (name "unconnected-(U9-SUSPND-Pad32)") (class "Default")
      (node (ref "U9") (pin "32") (pinfunction "SUSPND_32") (pintype "output"))
    )
    (net (code "42") (name "unconnected-(U11-IO1-Pad4)") (class "Default")
      (node (ref "U11") (pin "4") (pinfunction "IO1_4") (pintype "passive"))
    )
    (net (code "43") (name "unconnected-(U11-IO2-Pad3)") (class "Default")
      (node (ref "U11") (pin "3") (pinfunction "IO2_3") (pintype "passive"))
    )
    (net (code "44") (name "unconnected-(U13-IO1-Pad4)") (class "Default")
      (node (ref "U13") (pin "4") (pinfunction "IO1_4") (pintype "passive"))
    )
    (net (code "45") (name "unconnected-(U13-IO2-Pad3)") (class "Default")
      (node (ref "U13") (pin "3") (pinfunction "IO2_3") (pintype "passive"))
    )
  )
)
